# USB_SERIAL_QUAD.net
KiCad netlist of a schematic drawn in Altium Designer
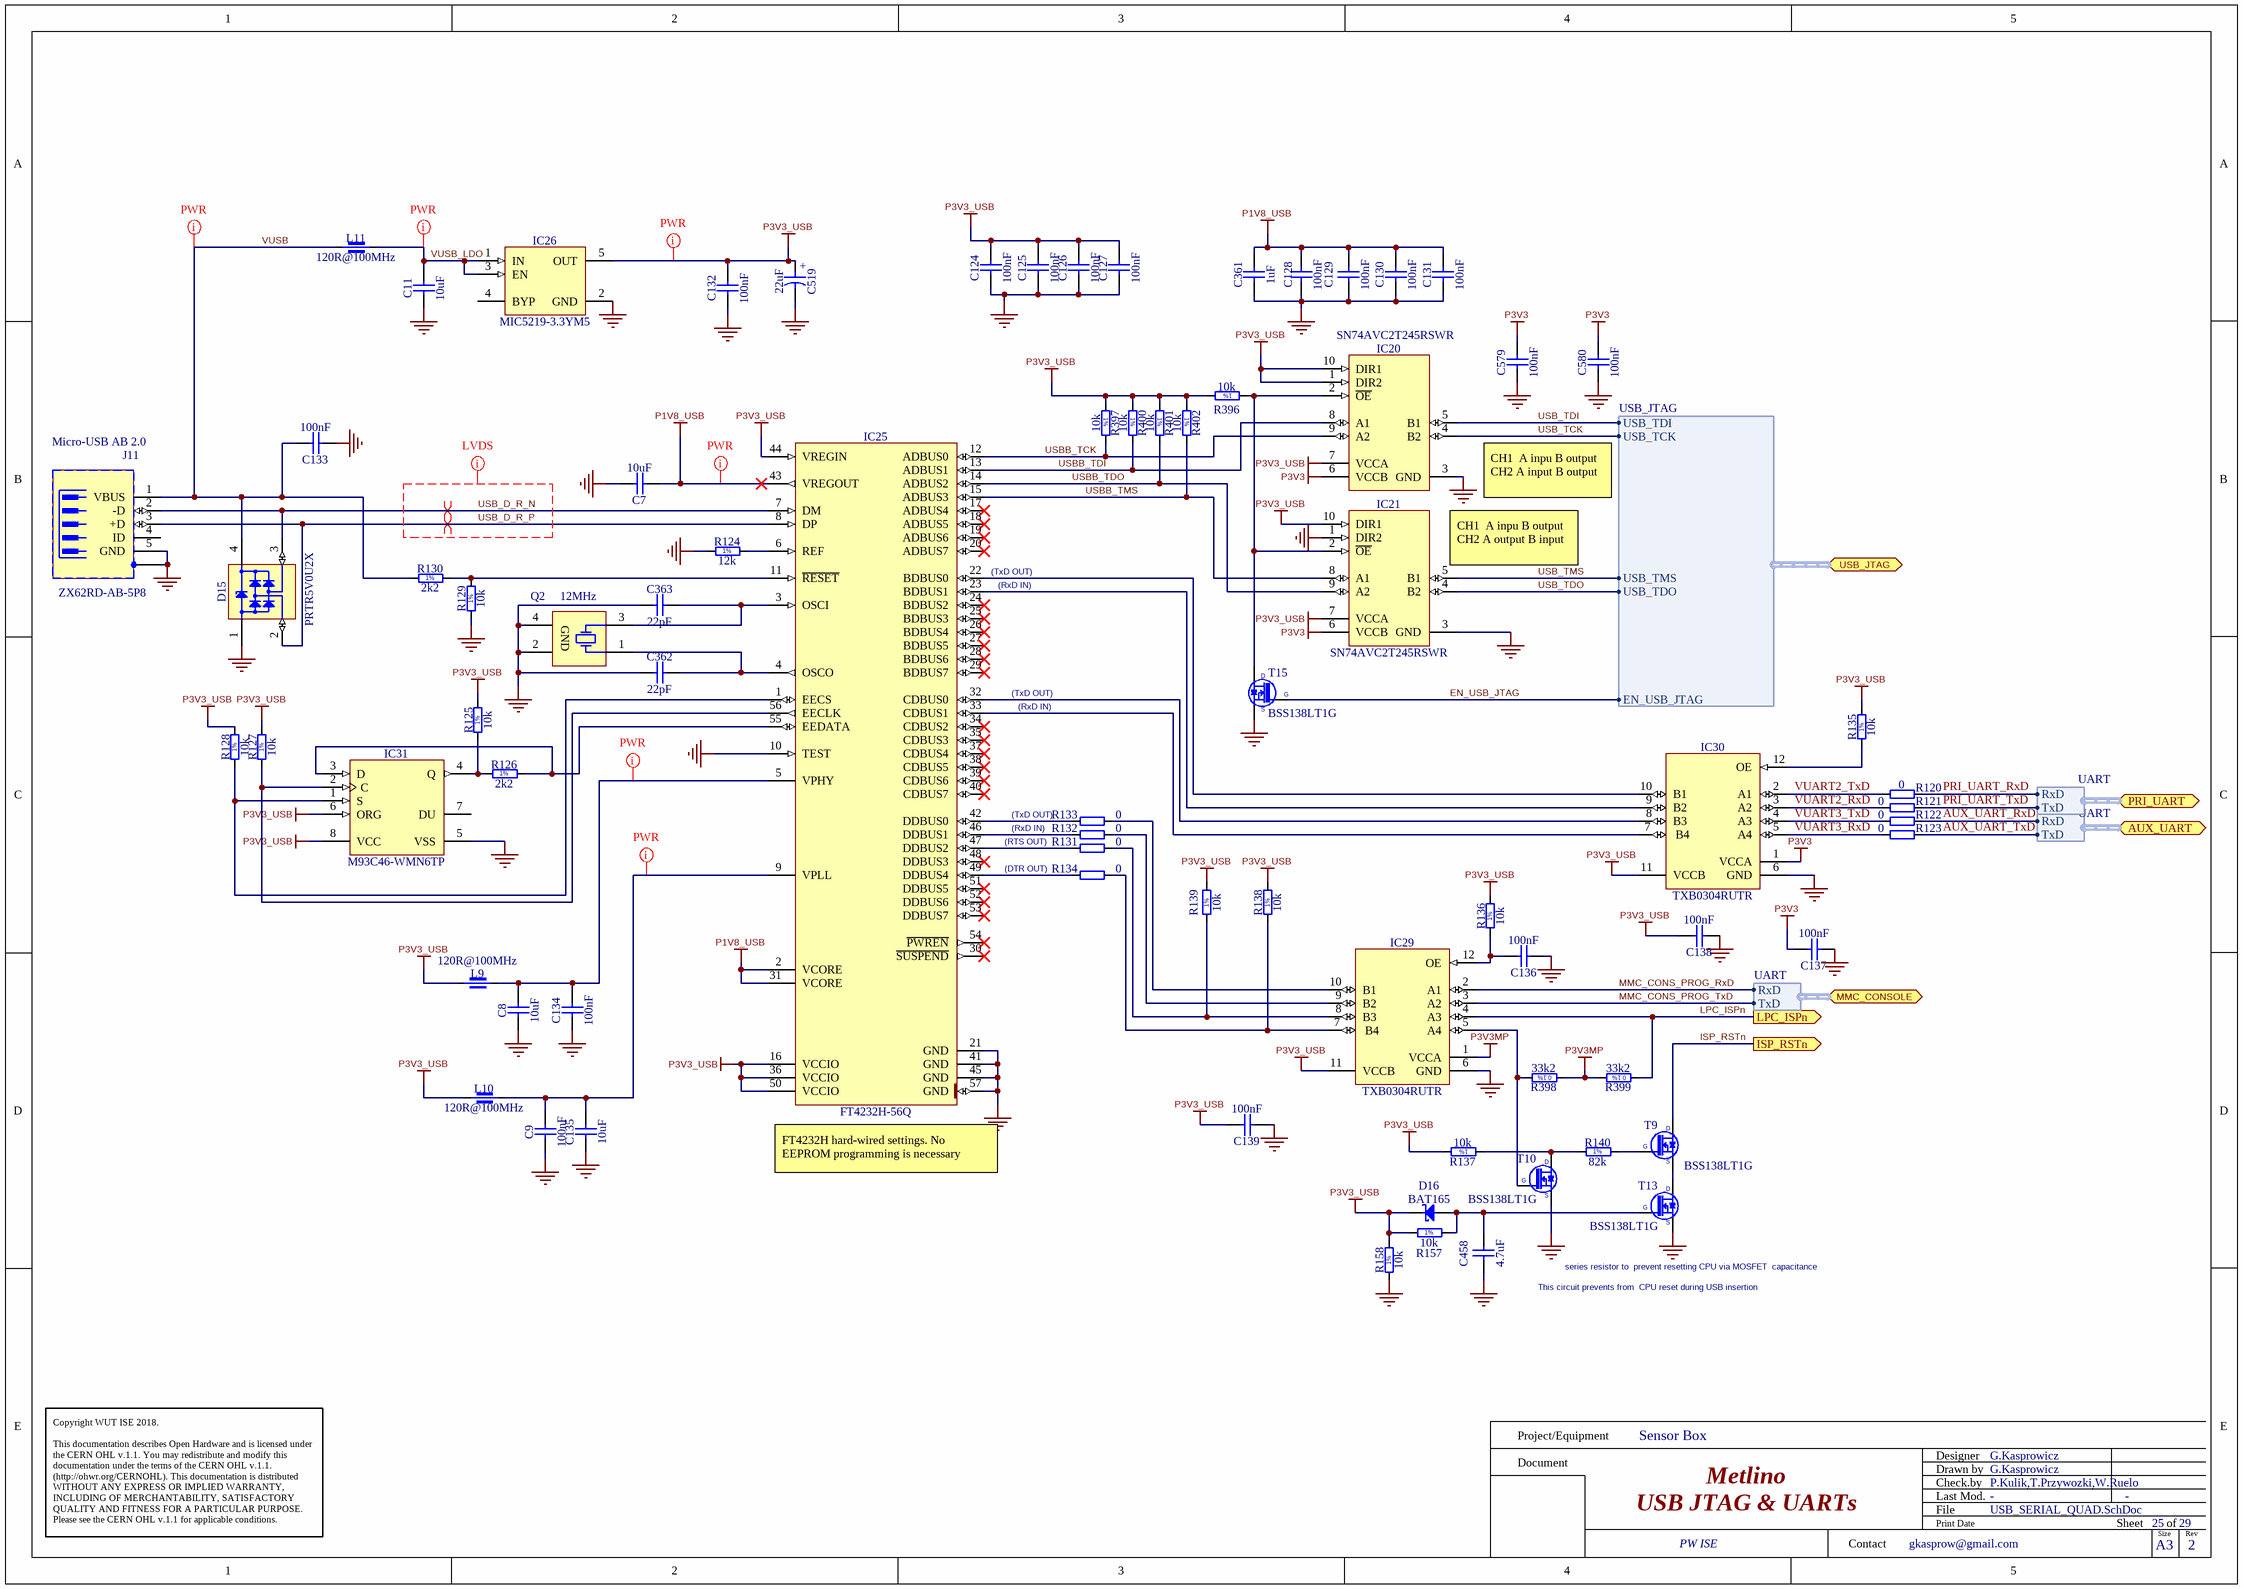
[diagram p0: USB_SERIAL_QUAD.SchDoc]

(export (version "E")
  (design (tool "Eeschema 10.0.6"))
  (components
    (comp (ref "C7")
      (value "10uF")
      (footprint "CAPC1608X87N")
      (description "Non-polarised capacitor")
      (fields
        (field (name "MANUFACTURER PART NUMBER") "CC0603_10uF_6.3V_20%_X5R")
        (field (name "MANUFACTURER") "GENERIC")
        (field (name "AUTHOR") "CERN DEM JLC")
      )
      (libsource (lib "Capacitors") (part "Capacitor - non polarized"))
    )
    (comp (ref "C8")
      (value "10uF")
      (footprint "CAPC1608X87N")
      (description "Non-polarised capacitor")
      (fields
        (field (name "MANUFACTURER PART NUMBER") "CC0603_10uF_6.3V_20%_X5R")
        (field (name "MANUFACTURER") "GENERIC")
        (field (name "AUTHOR") "CERN DEM JLC")
      )
      (libsource (lib "Capacitors") (part "Capacitor - non polarized"))
    )
    (comp (ref "C9")
      (value "100nF")
      (footprint "CAPC0603X33N")
      (description "Non-polarised capacitor")
      (fields
        (field (name "MANUFACTURER PART NUMBER") "CC0201_100NF_6.3V_10%_X5R")
        (field (name "MANUFACTURER") "GENERIC")
        (field (name "AUTHOR") "CERN DEM JLC")
      )
      (libsource (lib "Capacitors") (part "Capacitor - non polarized"))
    )
    (comp (ref "C11")
      (value "10uF")
      (footprint "CAPC1608X87N")
      (description "Non-polarised capacitor")
      (fields
        (field (name "MANUFACTURER PART NUMBER") "CC0603_10uF_6.3V_20%_X5R")
        (field (name "MANUFACTURER") "GENERIC")
        (field (name "AUTHOR") "CERN DEM JLC")
      )
      (libsource (lib "Capacitors") (part "Capacitor - non polarized"))
    )
    (comp (ref "C124")
      (value "100nF")
      (footprint "CAPC0603X33N")
      (description "Non-polarised capacitor")
      (fields
        (field (name "MANUFACTURER PART NUMBER") "CC0201_100NF_6.3V_10%_X5R")
        (field (name "MANUFACTURER") "GENERIC")
        (field (name "AUTHOR") "CERN DEM JLC")
      )
      (libsource (lib "Capacitors") (part "Capacitor - non polarized"))
    )
    (comp (ref "C125")
      (value "100nF")
      (footprint "CAPC0603X33N")
      (description "Non-polarised capacitor")
      (fields
        (field (name "MANUFACTURER PART NUMBER") "CC0201_100NF_6.3V_10%_X5R")
        (field (name "MANUFACTURER") "GENERIC")
        (field (name "AUTHOR") "CERN DEM JLC")
      )
      (libsource (lib "Capacitors") (part "Capacitor - non polarized"))
    )
    (comp (ref "C126")
      (value "100nF")
      (footprint "CAPC0603X33N")
      (description "Non-polarised capacitor")
      (fields
        (field (name "MANUFACTURER PART NUMBER") "CC0201_100NF_6.3V_10%_X5R")
        (field (name "MANUFACTURER") "GENERIC")
        (field (name "AUTHOR") "CERN DEM JLC")
      )
      (libsource (lib "Capacitors") (part "Capacitor - non polarized"))
    )
    (comp (ref "C127")
      (value "100nF")
      (footprint "CAPC0603X33N")
      (description "Non-polarised capacitor")
      (fields
        (field (name "MANUFACTURER PART NUMBER") "CC0201_100NF_6.3V_10%_X5R")
        (field (name "MANUFACTURER") "GENERIC")
        (field (name "AUTHOR") "CERN DEM JLC")
      )
      (libsource (lib "Capacitors") (part "Capacitor - non polarized"))
    )
    (comp (ref "C128")
      (value "100nF")
      (footprint "CAPC0603X33N")
      (description "Non-polarised capacitor")
      (fields
        (field (name "MANUFACTURER PART NUMBER") "CC0201_100NF_6.3V_10%_X5R")
        (field (name "MANUFACTURER") "GENERIC")
        (field (name "AUTHOR") "CERN DEM JLC")
      )
      (libsource (lib "Capacitors") (part "Capacitor - non polarized"))
    )
    (comp (ref "C129")
      (value "100nF")
      (footprint "CAPC0603X33N")
      (description "Non-polarised capacitor")
      (fields
        (field (name "MANUFACTURER PART NUMBER") "CC0201_100NF_6.3V_10%_X5R")
        (field (name "MANUFACTURER") "GENERIC")
        (field (name "AUTHOR") "CERN DEM JLC")
      )
      (libsource (lib "Capacitors") (part "Capacitor - non polarized"))
    )
    (comp (ref "C130")
      (value "100nF")
      (footprint "CAPC0603X33N")
      (description "Non-polarised capacitor")
      (fields
        (field (name "MANUFACTURER PART NUMBER") "CC0201_100NF_6.3V_10%_X5R")
        (field (name "MANUFACTURER") "GENERIC")
        (field (name "AUTHOR") "CERN DEM JLC")
      )
      (libsource (lib "Capacitors") (part "Capacitor - non polarized"))
    )
    (comp (ref "C131")
      (value "100nF")
      (footprint "CAPC0603X33N")
      (description "Non-polarised capacitor")
      (fields
        (field (name "MANUFACTURER PART NUMBER") "CC0201_100NF_6.3V_10%_X5R")
        (field (name "MANUFACTURER") "GENERIC")
        (field (name "AUTHOR") "CERN DEM JLC")
      )
      (libsource (lib "Capacitors") (part "Capacitor - non polarized"))
    )
    (comp (ref "C132")
      (value "100nF")
      (footprint "CAPC0603X33N")
      (description "Non-polarised capacitor")
      (fields
        (field (name "MANUFACTURER PART NUMBER") "CC0201_100NF_6.3V_10%_X5R")
        (field (name "MANUFACTURER") "GENERIC")
        (field (name "AUTHOR") "CERN DEM JLC")
      )
      (libsource (lib "Capacitors") (part "Capacitor - non polarized"))
    )
    (comp (ref "C133")
      (value "100nF")
      (footprint "CAPC0603X33N")
      (description "Non-polarised capacitor")
      (fields
        (field (name "MANUFACTURER PART NUMBER") "CC0201_100NF_6.3V_10%_X5R")
        (field (name "MANUFACTURER") "GENERIC")
        (field (name "AUTHOR") "CERN DEM JLC")
      )
      (libsource (lib "Capacitors") (part "Capacitor - non polarized"))
    )
    (comp (ref "C134")
      (value "100nF")
      (footprint "CAPC0603X33N")
      (description "Non-polarised capacitor")
      (fields
        (field (name "MANUFACTURER PART NUMBER") "CC0201_100NF_6.3V_10%_X5R")
        (field (name "MANUFACTURER") "GENERIC")
        (field (name "AUTHOR") "CERN DEM JLC")
      )
      (libsource (lib "Capacitors") (part "Capacitor - non polarized"))
    )
    (comp (ref "C135")
      (value "10uF")
      (footprint "CAPC1608X87N")
      (description "Non-polarised capacitor")
      (fields
        (field (name "MANUFACTURER PART NUMBER") "CC0603_10uF_6.3V_20%_X5R")
        (field (name "MANUFACTURER") "GENERIC")
        (field (name "AUTHOR") "CERN DEM JLC")
      )
      (libsource (lib "Capacitors") (part "Capacitor - non polarized"))
    )
    (comp (ref "C136")
      (value "100nF")
      (footprint "CAPC0603X33N")
      (description "Non-polarised capacitor")
      (fields
        (field (name "MANUFACTURER PART NUMBER") "CC0201_100NF_6.3V_10%_X5R")
        (field (name "MANUFACTURER") "GENERIC")
        (field (name "AUTHOR") "CERN DEM JLC")
      )
      (libsource (lib "Capacitors") (part "Capacitor - non polarized"))
    )
    (comp (ref "C137")
      (value "100nF")
      (footprint "CAPC0603X33N")
      (description "Non-polarised capacitor")
      (fields
        (field (name "MANUFACTURER PART NUMBER") "CC0201_100NF_6.3V_10%_X5R")
        (field (name "MANUFACTURER") "GENERIC")
        (field (name "AUTHOR") "CERN DEM JLC")
      )
      (libsource (lib "Capacitors") (part "Capacitor - non polarized"))
    )
    (comp (ref "C138")
      (value "100nF")
      (footprint "CAPC0603X33N")
      (description "Non-polarised capacitor")
      (fields
        (field (name "MANUFACTURER PART NUMBER") "CC0201_100NF_6.3V_10%_X5R")
        (field (name "MANUFACTURER") "GENERIC")
        (field (name "AUTHOR") "CERN DEM JLC")
      )
      (libsource (lib "Capacitors") (part "Capacitor - non polarized"))
    )
    (comp (ref "C139")
      (value "100nF")
      (footprint "CAPC0603X33N")
      (description "Non-polarised capacitor")
      (fields
        (field (name "MANUFACTURER PART NUMBER") "CC0201_100NF_6.3V_10%_X5R")
        (field (name "MANUFACTURER") "GENERIC")
        (field (name "AUTHOR") "CERN DEM JLC")
      )
      (libsource (lib "Capacitors") (part "Capacitor - non polarized"))
    )
    (comp (ref "C361")
      (value "1uF")
      (footprint "CAPC1005X55N")
      (description "Non-polarised capacitor")
      (fields
        (field (name "MANUFACTURER PART NUMBER") "CC0402_1UF_16V_10%_X5R")
        (field (name "MANUFACTURER") "GENERIC")
        (field (name "AUTHOR") "CERN DEM JLC")
      )
      (libsource (lib "Capacitors") (part "Capacitor - non polarized"))
    )
    (comp (ref "C362")
      (value "22pF")
      (footprint "CAPC1005X55N")
      (description "Non-polarised capacitor")
      (fields
        (field (name "MANUFACTURER PART NUMBER") "CC0402_22PF_50V_5%_C0G")
        (field (name "MANUFACTURER") "GENERIC")
        (field (name "AUTHOR") "CERN DEM JLC")
      )
      (libsource (lib "Capacitors") (part "Capacitor - non polarized"))
    )
    (comp (ref "C363")
      (value "22pF")
      (footprint "CAPC1005X55N")
      (description "Non-polarised capacitor")
      (fields
        (field (name "MANUFACTURER PART NUMBER") "CC0402_22PF_50V_5%_C0G")
        (field (name "MANUFACTURER") "GENERIC")
        (field (name "AUTHOR") "CERN DEM JLC")
      )
      (libsource (lib "Capacitors") (part "Capacitor - non polarized"))
    )
    (comp (ref "C458")
      (value "4.7uF")
      (footprint "CAPC1709X95N")
      (description "Non-polarised capacitor")
      (fields
        (field (name "MANUFACTURER PART NUMBER") "CC0603_4.7UF_16V_10%_X5R")
        (field (name "MANUFACTURER") "GENERIC")
        (field (name "AUTHOR") "CERN DEM JLC")
      )
      (libsource (lib "Capacitors") (part "Capacitor - non polarized"))
    )
    (comp (ref "C519")
      (value "22uF")
      (footprint "CAPMP3216X180N")
      (description "Polarised capacitor")
      (fields
        (field (name "MANUFACTURER PART NUMBER") "CTE3216-18_22UF_6.3V_10%_LESR0900")
        (field (name "MANUFACTURER") "GENERIC")
        (field (name "AUTHOR") "CERN DEM JLC")
      )
      (libsource (lib "Capacitors") (part "Capacitor - polarized"))
    )
    (comp (ref "C579")
      (value "100nF")
      (footprint "CAPC0603X33N")
      (description "Non-polarised capacitor")
      (fields
        (field (name "MANUFACTURER PART NUMBER") "CC0201_100NF_6.3V_10%_X5R")
        (field (name "MANUFACTURER") "GENERIC")
        (field (name "AUTHOR") "CERN DEM JLC")
      )
      (libsource (lib "Capacitors") (part "Capacitor - non polarized"))
    )
    (comp (ref "C580")
      (value "100nF")
      (footprint "CAPC0603X33N")
      (description "Non-polarised capacitor")
      (fields
        (field (name "MANUFACTURER PART NUMBER") "CC0201_100NF_6.3V_10%_X5R")
        (field (name "MANUFACTURER") "GENERIC")
        (field (name "AUTHOR") "CERN DEM JLC")
      )
      (libsource (lib "Capacitors") (part "Capacitor - non polarized"))
    )
    (comp (ref "D15")
      (value "PRTR5V0U2X")
      (footprint "SOT190P230X110-4N")
      (description "Ultra Low Capacitance Double Rail-to-Rail ESD Protection Diode")
      (fields
        (field (name "MANUFACTURER") "NXP SEMICONDUCTORS")
        (field (name "VOLTAGE") "5.5V")
        (field (name "AUTHOR") "CERN DEM JLC")
      )
      (libsource (lib "ICs And Semiconductors") (part "PRTR5V0U2X"))
    )
    (comp (ref "D16")
      (value "BAT165")
      (footprint "SOD2512X110N")
      (description "Schottky Diode")
      (fields
        (field (name "MANUFACTURER") "INFINEON")
        (field (name "VOLTAGE") "40V")
        (field (name "AUTHOR") "CERN DEM JLC")
      )
      (libsource (lib "ICs And Semiconductors") (part "Diode Schottky"))
    )
    (comp (ref "IC20")
      (value "SN74AVC2T245RSWR")
      (footprint "QFN40P140X180X55-10N")
      (description "Dual-Bit Dual-Supply Bus Transceiver With Configurable Voltage Translation and 3-State Outputs")
      (fields (field (name "MANUFACTURER") "TEXAS INSTRUMENTS") (field (name "AUTHOR") "CERN DEM JLC"))
      (libsource (lib "ICs And Semiconductors") (part "742T245"))
    )
    (comp (ref "IC21")
      (value "SN74AVC2T245RSWR")
      (footprint "QFN40P140X180X55-10N")
      (description "Dual-Bit Dual-Supply Bus Transceiver With Configurable Voltage Translation and 3-State Outputs")
      (fields (field (name "MANUFACTURER") "TEXAS INSTRUMENTS") (field (name "AUTHOR") "CERN DEM JLC"))
      (libsource (lib "ICs And Semiconductors") (part "742T245"))
    )
    (comp (ref "IC25")
      (value "FT4232H-56Q")
      (footprint "QFN50P800X800X100-57N-S620")
      (description "Quad High Speed USB to Multipurpose UART/MPSSE IC")
      (fields
        (field (name "MANUFACTURER") "FUTURE TECHNOLOGY DEVICES INTERNATIONAL (FTDI)")
        (field (name "AUTHOR") "CERN DEM JLC")
      )
      (libsource (lib "ICs And Semiconductors") (part "FT4232H-56Q"))
    )
    (comp (ref "IC26")
      (value "MIC5219-3.3YM5")
      (footprint "SOT95P280X145-5N")
      (description "500mA Peak Output LDO Regulator")
      (fields (field (name "MANUFACTURER") "MICROCHIP TECHNOLOGY") (field (name "AUTHOR") "CERN DEM WB"))
      (libsource (lib "ICs And Semiconductors") (part "MIC5219-X.XYM5"))
    )
    (comp (ref "IC29")
      (value "TXB0304RUTR")
      (footprint "TEXAS_RUT (R-PUQFN-N12)")
      (description "4-bit Bidirectional Auto-direction Sensing Translator with Fully Symmetric 0.9V to 3.6V Range")
      (fields (field (name "MANUFACTURER") "TEXAS INSTRUMENTS") (field (name "AUTHOR") "CERN DEM JLC"))
      (libsource (lib "ICs And Semiconductors") (part "TXB0304RUTR"))
    )
    (comp (ref "IC30")
      (value "TXB0304RUTR")
      (footprint "TEXAS_RUT (R-PUQFN-N12)")
      (description "4-bit Bidirectional Auto-direction Sensing Translator with Fully Symmetric 0.9V to 3.6V Range")
      (fields (field (name "MANUFACTURER") "TEXAS INSTRUMENTS") (field (name "AUTHOR") "CERN DEM JLC"))
      (libsource (lib "ICs And Semiconductors") (part "TXB0304RUTR"))
    )
    (comp (ref "IC31")
      (value "M93C46-WMN6TP")
      (footprint "SOIC127P600X175-8N")
      (description "2.5 to 5.5 V, 1Kb (128x8) Serial Microwire Bus EEPROM")
      (fields (field (name "MANUFACTURER") "ST MICROELECTRONICS") (field (name "AUTHOR") "CERN DEM JLC"))
      (libsource (lib "ICs And Semiconductors") (part "M93C46-WMN6TP"))
    )
    (comp (ref "J11")
      (value "Micro-USB AB 2.0")
      (footprint "HIROSE_ZX62RD-AB-5P8")
      (description "5 Pin + 1 Shield USB Receptacle")
      (fields
        (field (name "MANUFACTURER PART NUMBER") "ZX62RD-AB-5P8")
        (field (name "MANUFACTURER") "HIROSE (HRS)")
        (field (name "PART NUMBER") "HIROSE_ZX62RD-AB-5P8")
        (field (name "AUTHOR") "CERN DEM JLC")
      )
      (libsource (lib "Connectors") (part "Connector USB 5 Pin + 1Shield"))
    )
    (comp (ref "L9")
      (value "120R@100MHz")
      (footprint "INDC1608X65N")
      (fields
        (field (name "MANUFACTURER PART NUMBER") "BLM18SG121TN1D")
        (field (name "MANUFACTURER") "MURATA")
        (field (name "PART NUMBER") "IND0603_MURATA_BLM18SG121TN1D")
        (field (name "AUTHOR") "CERN DEM JLC")
      )
      (libsource (lib "Inductors & Transformers") (part "Ferrite Bead"))
    )
    (comp (ref "L10")
      (value "120R@100MHz")
      (footprint "INDC1608X65N")
      (fields
        (field (name "MANUFACTURER PART NUMBER") "BLM18SG121TN1D")
        (field (name "MANUFACTURER") "MURATA")
        (field (name "PART NUMBER") "IND0603_MURATA_BLM18SG121TN1D")
        (field (name "AUTHOR") "CERN DEM JLC")
      )
      (libsource (lib "Inductors & Transformers") (part "Ferrite Bead"))
    )
    (comp (ref "L11")
      (value "120R@100MHz")
      (footprint "INDC1608X65N")
      (fields
        (field (name "MANUFACTURER PART NUMBER") "BLM18SG121TN1D")
        (field (name "MANUFACTURER") "MURATA")
        (field (name "PART NUMBER") "IND0603_MURATA_BLM18SG121TN1D")
        (field (name "AUTHOR") "CERN DEM JLC")
      )
      (libsource (lib "Inductors & Transformers") (part "Ferrite Bead"))
    )
    (comp (ref "Q2")
      (value "12MHz")
      (footprint "XTAL_TXC_7M")
      (description "Crystal 4 pins 1=XTAL Control 2=GND3=XTAL 4=GND")
      (fields
        (field (name "MANUFACTURER PART NUMBER") "7M-12.000MAAJ-T")
        (field (name "MANUFACTURER") "TXC CORPORATION")
        (field (name "AUTHOR") "CERN DEM JLC")
      )
      (libsource (lib "ICs And Semiconductors") (part "Quartz Crystal 1X 2GND 3X 4GND"))
    )
    (comp (ref "R120")
      (value "0")
      (footprint "RESC1005X40N")
      (description "Resistor")
      (fields
        (field (name "MANUFACTURER PART NUMBER") "R0402_0R_JUMPER")
        (field (name "MANUFACTURER") "GENERIC")
        (field (name "AUTHOR") "CERN DEM JLC")
      )
      (libsource (lib "Resistors") (part "Resistor"))
    )
    (comp (ref "R121")
      (value "0")
      (footprint "RESC1005X40N")
      (description "Resistor")
      (fields
        (field (name "MANUFACTURER PART NUMBER") "R0402_0R_JUMPER")
        (field (name "MANUFACTURER") "GENERIC")
        (field (name "AUTHOR") "CERN DEM JLC")
      )
      (libsource (lib "Resistors") (part "Resistor"))
    )
    (comp (ref "R122")
      (value "0")
      (footprint "RESC1005X40N")
      (description "Resistor")
      (fields
        (field (name "MANUFACTURER PART NUMBER") "R0402_0R_JUMPER")
        (field (name "MANUFACTURER") "GENERIC")
        (field (name "AUTHOR") "CERN DEM JLC")
      )
      (libsource (lib "Resistors") (part "Resistor"))
    )
    (comp (ref "R123")
      (value "0")
      (footprint "RESC1005X40N")
      (description "Resistor")
      (fields
        (field (name "MANUFACTURER PART NUMBER") "R0402_0R_JUMPER")
        (field (name "MANUFACTURER") "GENERIC")
        (field (name "AUTHOR") "CERN DEM JLC")
      )
      (libsource (lib "Resistors") (part "Resistor"))
    )
    (comp (ref "R124")
      (value "12k")
      (footprint "RESC1005X40N")
      (description "Resistor - 1%")
      (fields
        (field (name "MANUFACTURER PART NUMBER") "R0402_12K_1%_0.0625W_100PPM")
        (field (name "MANUFACTURER") "GENERIC")
        (field (name "AUTHOR") "CERN DEM JLC")
      )
      (libsource (lib "Resistors") (part "Resistor - 1%"))
    )
    (comp (ref "R125")
      (value "10k")
      (footprint "RESC1005X40N")
      (description "Resistor - 1%")
      (fields
        (field (name "MANUFACTURER PART NUMBER") "R0402_10K_1%_0.0625W_100PPM")
        (field (name "MANUFACTURER") "GENERIC")
        (field (name "AUTHOR") "CERN DEM JLC")
      )
      (libsource (lib "Resistors") (part "Resistor - 1%"))
    )
    (comp (ref "R126")
      (value "2k2")
      (footprint "RESC1005X40N")
      (description "Resistor - 1%")
      (fields
        (field (name "MANUFACTURER PART NUMBER") "R0402_2K2_1%_0.0625W_100PPM")
        (field (name "MANUFACTURER") "GENERIC")
        (field (name "AUTHOR") "CERN DEM JLC")
      )
      (libsource (lib "Resistors") (part "Resistor - 1%"))
    )
    (comp (ref "R127")
      (value "10k")
      (footprint "RESC1005X40N")
      (description "Resistor - 1%")
      (fields
        (field (name "MANUFACTURER PART NUMBER") "R0402_10K_1%_0.0625W_100PPM")
        (field (name "MANUFACTURER") "GENERIC")
        (field (name "AUTHOR") "CERN DEM JLC")
      )
      (libsource (lib "Resistors") (part "Resistor - 1%"))
    )
    (comp (ref "R128")
      (value "10k")
      (footprint "RESC1005X40N")
      (description "Resistor - 1%")
      (fields
        (field (name "MANUFACTURER PART NUMBER") "R0402_10K_1%_0.0625W_100PPM")
        (field (name "MANUFACTURER") "GENERIC")
        (field (name "AUTHOR") "CERN DEM JLC")
      )
      (libsource (lib "Resistors") (part "Resistor - 1%"))
    )
    (comp (ref "R129")
      (value "10k")
      (footprint "RESC1005X40N")
      (description "Resistor - 1%")
      (fields
        (field (name "MANUFACTURER PART NUMBER") "R0402_10K_1%_0.0625W_100PPM")
        (field (name "MANUFACTURER") "GENERIC")
        (field (name "AUTHOR") "CERN DEM JLC")
      )
      (libsource (lib "Resistors") (part "Resistor - 1%"))
    )
    (comp (ref "R130")
      (value "2k2")
      (footprint "RESC1005X40N")
      (description "Resistor - 1%")
      (fields
        (field (name "MANUFACTURER PART NUMBER") "R0402_2K2_1%_0.0625W_100PPM")
        (field (name "MANUFACTURER") "GENERIC")
        (field (name "AUTHOR") "CERN DEM JLC")
      )
      (libsource (lib "Resistors") (part "Resistor - 1%"))
    )
    (comp (ref "R131")
      (value "0")
      (footprint "RESC1005X40N")
      (description "Resistor")
      (fields
        (field (name "MANUFACTURER PART NUMBER") "R0402_0R_JUMPER")
        (field (name "MANUFACTURER") "GENERIC")
        (field (name "AUTHOR") "CERN DEM JLC")
      )
      (libsource (lib "Resistors") (part "Resistor"))
    )
    (comp (ref "R132")
      (value "0")
      (footprint "RESC1005X40N")
      (description "Resistor")
      (fields
        (field (name "MANUFACTURER PART NUMBER") "R0402_0R_JUMPER")
        (field (name "MANUFACTURER") "GENERIC")
        (field (name "AUTHOR") "CERN DEM JLC")
      )
      (libsource (lib "Resistors") (part "Resistor"))
    )
    (comp (ref "R133")
      (value "0")
      (footprint "RESC1005X40N")
      (description "Resistor")
      (fields
        (field (name "MANUFACTURER PART NUMBER") "R0402_0R_JUMPER")
        (field (name "MANUFACTURER") "GENERIC")
        (field (name "AUTHOR") "CERN DEM JLC")
      )
      (libsource (lib "Resistors") (part "Resistor"))
    )
    (comp (ref "R134")
      (value "0")
      (footprint "RESC1005X40N")
      (description "Resistor")
      (fields
        (field (name "MANUFACTURER PART NUMBER") "R0402_0R_JUMPER")
        (field (name "MANUFACTURER") "GENERIC")
        (field (name "AUTHOR") "CERN DEM JLC")
      )
      (libsource (lib "Resistors") (part "Resistor"))
    )
    (comp (ref "R135")
      (value "10k")
      (footprint "RESC1005X40N")
      (description "Resistor - 1%")
      (fields
        (field (name "MANUFACTURER PART NUMBER") "R0402_10K_1%_0.0625W_100PPM")
        (field (name "MANUFACTURER") "GENERIC")
        (field (name "AUTHOR") "CERN DEM JLC")
      )
      (libsource (lib "Resistors") (part "Resistor - 1%"))
    )
    (comp (ref "R136")
      (value "10k")
      (footprint "RESC1005X40N")
      (description "Resistor - 1%")
      (fields
        (field (name "MANUFACTURER PART NUMBER") "R0402_10K_1%_0.0625W_100PPM")
        (field (name "MANUFACTURER") "GENERIC")
        (field (name "AUTHOR") "CERN DEM JLC")
      )
      (libsource (lib "Resistors") (part "Resistor - 1%"))
    )
    (comp (ref "R137")
      (value "10k")
      (footprint "RESC1005X40N")
      (description "Resistor - 1%")
      (fields
        (field (name "MANUFACTURER PART NUMBER") "R0402_10K_1%_0.0625W_100PPM")
        (field (name "MANUFACTURER") "GENERIC")
        (field (name "AUTHOR") "CERN DEM JLC")
      )
      (libsource (lib "Resistors") (part "Resistor - 1%"))
    )
    (comp (ref "R138")
      (value "10k")
      (footprint "RESC1005X40N")
      (description "Resistor - 1%")
      (fields
        (field (name "MANUFACTURER PART NUMBER") "R0402_10K_1%_0.0625W_100PPM")
        (field (name "MANUFACTURER") "GENERIC")
        (field (name "AUTHOR") "CERN DEM JLC")
      )
      (libsource (lib "Resistors") (part "Resistor - 1%"))
    )
    (comp (ref "R139")
      (value "10k")
      (footprint "RESC1005X40N")
      (description "Resistor - 1%")
      (fields
        (field (name "MANUFACTURER PART NUMBER") "R0402_10K_1%_0.0625W_100PPM")
        (field (name "MANUFACTURER") "GENERIC")
        (field (name "AUTHOR") "CERN DEM JLC")
      )
      (libsource (lib "Resistors") (part "Resistor - 1%"))
    )
    (comp (ref "R140")
      (value "82k")
      (footprint "RESC1005X40N")
      (description "Resistor - 1%")
      (fields
        (field (name "MANUFACTURER PART NUMBER") "R0402_82K_1%_0.0625W_100PPM")
        (field (name "MANUFACTURER") "GENERIC")
        (field (name "AUTHOR") "CERN DEM JLC")
      )
      (libsource (lib "Resistors") (part "Resistor - 1%"))
    )
    (comp (ref "R157")
      (value "10k")
      (footprint "RESC1005X40N")
      (description "Resistor - 1%")
      (fields
        (field (name "MANUFACTURER PART NUMBER") "R0402_10K_1%_0.0625W_100PPM")
        (field (name "MANUFACTURER") "GENERIC")
        (field (name "AUTHOR") "CERN DEM JLC")
      )
      (libsource (lib "Resistors") (part "Resistor - 1%"))
    )
    (comp (ref "R158")
      (value "10k")
      (footprint "RESC1005X40N")
      (description "Resistor - 1%")
      (fields
        (field (name "MANUFACTURER PART NUMBER") "R0402_10K_1%_0.0625W_100PPM")
        (field (name "MANUFACTURER") "GENERIC")
        (field (name "AUTHOR") "CERN DEM JLC")
      )
      (libsource (lib "Resistors") (part "Resistor - 1%"))
    )
    (comp (ref "R396")
      (value "10k")
      (footprint "RESC1005X40N")
      (description "Resistor - 1%")
      (fields
        (field (name "MANUFACTURER PART NUMBER") "R0402_10K_1%_0.0625W_100PPM")
        (field (name "MANUFACTURER") "GENERIC")
        (field (name "AUTHOR") "CERN DEM JLC")
      )
      (libsource (lib "Resistors") (part "Resistor - 1%"))
    )
    (comp (ref "R397")
      (value "10k")
      (footprint "RESC1005X40N")
      (description "Resistor - 1%")
      (fields
        (field (name "MANUFACTURER PART NUMBER") "R0402_10K_1%_0.0625W_100PPM")
        (field (name "MANUFACTURER") "GENERIC")
        (field (name "AUTHOR") "CERN DEM JLC")
      )
      (libsource (lib "Resistors") (part "Resistor - 1%"))
    )
    (comp (ref "R398")
      (value "33k2")
      (footprint "RESC1608X55N")
      (description "Resistor - 0.1%")
      (fields
        (field (name "MANUFACTURER PART NUMBER") "R0603_33K2_0.1%_0.063W_10PPM")
        (field (name "MANUFACTURER") "GENERIC")
        (field (name "AUTHOR") "CERN DEM JLC")
      )
      (libsource (lib "Resistors") (part "Resistor - 0.1%"))
    )
    (comp (ref "R399")
      (value "33k2")
      (footprint "RESC1608X55N")
      (description "Resistor - 0.1%")
      (fields
        (field (name "MANUFACTURER PART NUMBER") "R0603_33K2_0.1%_0.063W_10PPM")
        (field (name "MANUFACTURER") "GENERIC")
        (field (name "AUTHOR") "CERN DEM JLC")
      )
      (libsource (lib "Resistors") (part "Resistor - 0.1%"))
    )
    (comp (ref "R400")
      (value "10k")
      (footprint "RESC1005X40N")
      (description "Resistor - 1%")
      (fields
        (field (name "MANUFACTURER PART NUMBER") "R0402_10K_1%_0.0625W_100PPM")
        (field (name "MANUFACTURER") "GENERIC")
        (field (name "AUTHOR") "CERN DEM JLC")
      )
      (libsource (lib "Resistors") (part "Resistor - 1%"))
    )
    (comp (ref "R401")
      (value "10k")
      (footprint "RESC1005X40N")
      (description "Resistor - 1%")
      (fields
        (field (name "MANUFACTURER PART NUMBER") "R0402_10K_1%_0.0625W_100PPM")
        (field (name "MANUFACTURER") "GENERIC")
        (field (name "AUTHOR") "CERN DEM JLC")
      )
      (libsource (lib "Resistors") (part "Resistor - 1%"))
    )
    (comp (ref "R402")
      (value "10k")
      (footprint "RESC1005X40N")
      (description "Resistor - 1%")
      (fields
        (field (name "MANUFACTURER PART NUMBER") "R0402_10K_1%_0.0625W_100PPM")
        (field (name "MANUFACTURER") "GENERIC")
        (field (name "AUTHOR") "CERN DEM JLC")
      )
      (libsource (lib "Resistors") (part "Resistor - 1%"))
    )
    (comp (ref "T9")
      (value "BSS138LT1G")
      (footprint "SOT95P240X110-3N")
      (description "N-CHANNEL MOSFET WITH DIODE")
      (fields (field (name "MANUFACTURER") "ON SEMICONDUCTOR") (field (name "AUTHOR") "CERN DEM JLC"))
      (libsource (lib "ICs And Semiconductors") (part "N-MOSFET-D 1G 2S 3D"))
    )
    (comp (ref "T10")
      (value "BSS138LT1G")
      (footprint "SOT95P240X110-3N")
      (description "N-CHANNEL MOSFET WITH DIODE")
      (fields (field (name "MANUFACTURER") "ON SEMICONDUCTOR") (field (name "AUTHOR") "CERN DEM JLC"))
      (libsource (lib "ICs And Semiconductors") (part "N-MOSFET-D 1G 2S 3D"))
    )
    (comp (ref "T13")
      (value "BSS138LT1G")
      (footprint "SOT95P240X110-3N")
      (description "N-CHANNEL MOSFET WITH DIODE")
      (fields (field (name "MANUFACTURER") "ON SEMICONDUCTOR") (field (name "AUTHOR") "CERN DEM JLC"))
      (libsource (lib "ICs And Semiconductors") (part "N-MOSFET-D 1G 2S 3D"))
    )
    (comp (ref "T15")
      (value "BSS138LT1G")
      (footprint "SOT95P240X110-3N")
      (description "N-CHANNEL MOSFET WITH DIODE")
      (fields (field (name "MANUFACTURER") "ON SEMICONDUCTOR") (field (name "AUTHOR") "CERN DEM JLC"))
      (libsource (lib "") (part "N-MOSFET-D 1G 2S 3D_1"))
    )
  )
  (nets
    (net (code "4") (name "/AUX_UART_RxD") (class "Default")
      (node (ref "R122") (pin "1") (pinfunction "1_1") (pintype "passive"))
    )
    (net (code "5") (name "/AUX_UART_TxD") (class "Default")
      (node (ref "R123") (pin "1") (pinfunction "1_1") (pintype "passive"))
    )
    (net (code "6") (name "/EN_USB_JTAG") (class "Default")
      (node (ref "T15") (pin "1") (pinfunction "G_1") (pintype "passive"))
    )
    (net (code "7") (name "/ISP_RSTn") (class "Default")
      (node (ref "T9") (pin "3") (pinfunction "D_3") (pintype "passive"))
    )
    (net (code "8") (name "/LPC_ISPn") (class "Default")
      (node (ref "IC29") (pin "4") (pinfunction "A3_4") (pintype "bidirectional"))
      (node (ref "R399") (pin "1") (pinfunction "1_1") (pintype "passive"))
    )
    (net (code "9") (name "/MMC_CONS_PROG_RxD") (class "Default")
      (node (ref "IC29") (pin "2") (pinfunction "A1_2") (pintype "bidirectional"))
    )
    (net (code "10") (name "/MMC_CONS_PROG_TxD") (class "Default")
      (node (ref "IC29") (pin "3") (pinfunction "A2_3") (pintype "bidirectional"))
    )
    (net (code "11") (name "/PRI_UART_RxD") (class "Default")
      (node (ref "R120") (pin "1") (pinfunction "1_1") (pintype "passive"))
    )
    (net (code "12") (name "/PRI_UART_TxD") (class "Default")
      (node (ref "R121") (pin "1") (pinfunction "1_1") (pintype "passive"))
    )
    (net (code "14") (name "/USBB_TCK") (class "Default")
      (node (ref "IC20") (pin "9") (pinfunction "A2_9") (pintype "bidirectional"))
      (node (ref "IC25") (pin "12") (pinfunction "ADBUS0_12") (pintype "bidirectional"))
      (node (ref "R397") (pin "2") (pinfunction "2_2") (pintype "passive"))
    )
    (net (code "15") (name "/USBB_TDI") (class "Default")
      (node (ref "IC20") (pin "8") (pinfunction "A1_8") (pintype "bidirectional"))
      (node (ref "IC25") (pin "13") (pinfunction "ADBUS1_13") (pintype "bidirectional"))
      (node (ref "R400") (pin "2") (pinfunction "2_2") (pintype "passive"))
    )
    (net (code "16") (name "/USBB_TDO") (class "Default")
      (node (ref "IC21") (pin "9") (pinfunction "A2_9") (pintype "bidirectional"))
      (node (ref "IC25") (pin "14") (pinfunction "ADBUS2_14") (pintype "bidirectional"))
      (node (ref "R401") (pin "2") (pinfunction "2_2") (pintype "passive"))
    )
    (net (code "17") (name "/USBB_TMS") (class "Default")
      (node (ref "IC21") (pin "8") (pinfunction "A1_8") (pintype "bidirectional"))
      (node (ref "IC25") (pin "15") (pinfunction "ADBUS3_15") (pintype "bidirectional"))
      (node (ref "R402") (pin "2") (pinfunction "2_2") (pintype "passive"))
    )
    (net (code "18") (name "/USB_D_R_N") (class "Default")
      (node (ref "D15") (pin "3") (pinfunction "I/O2_3") (pintype "bidirectional"))
      (node (ref "IC25") (pin "7") (pinfunction "DM_7") (pintype "input"))
      (node (ref "J11") (pin "2") (pinfunction "-D_2") (pintype "bidirectional"))
    )
    (net (code "19") (name "/USB_D_R_P") (class "Default")
      (node (ref "D15") (pin "2") (pinfunction "I/O1_2") (pintype "bidirectional"))
      (node (ref "IC25") (pin "8") (pinfunction "DP_8") (pintype "input"))
      (node (ref "J11") (pin "3") (pinfunction "+D_3") (pintype "bidirectional"))
    )
    (net (code "20") (name "/USB_TCK") (class "Default")
      (node (ref "IC20") (pin "4") (pinfunction "B2_4") (pintype "bidirectional"))
    )
    (net (code "21") (name "/USB_TDI") (class "Default")
      (node (ref "IC20") (pin "5") (pinfunction "B1_5") (pintype "bidirectional"))
    )
    (net (code "22") (name "/USB_TDO") (class "Default")
      (node (ref "IC21") (pin "4") (pinfunction "B2_4") (pintype "bidirectional"))
    )
    (net (code "23") (name "/USB_TMS") (class "Default")
      (node (ref "IC21") (pin "5") (pinfunction "B1_5") (pintype "bidirectional"))
    )
    (net (code "24") (name "/VUART2_RxD") (class "Default")
      (node (ref "IC30") (pin "3") (pinfunction "A2_3") (pintype "bidirectional"))
      (node (ref "R121") (pin "2") (pinfunction "2_2") (pintype "passive"))
    )
    (net (code "25") (name "/VUART2_TxD") (class "Default")
      (node (ref "IC30") (pin "2") (pinfunction "A1_2") (pintype "bidirectional"))
      (node (ref "R120") (pin "2") (pinfunction "2_2") (pintype "passive"))
    )
    (net (code "26") (name "/VUART3_RxD") (class "Default")
      (node (ref "IC30") (pin "5") (pinfunction "A4_5") (pintype "bidirectional"))
      (node (ref "R123") (pin "2") (pinfunction "2_2") (pintype "passive"))
    )
    (net (code "27") (name "/VUART3_TxD") (class "Default")
      (node (ref "IC30") (pin "4") (pinfunction "A3_4") (pintype "bidirectional"))
      (node (ref "R122") (pin "2") (pinfunction "2_2") (pintype "passive"))
    )
    (net (code "28") (name "/VUSB") (class "Default")
      (node (ref "C133") (pin "2") (pinfunction "2_2") (pintype "passive"))
      (node (ref "D15") (pin "4") (pinfunction "VCC_4") (pintype "power_in"))
      (node (ref "J11") (pin "1") (pinfunction "VBUS_1") (pintype "power_in"))
      (node (ref "L11") (pin "1") (pinfunction "1_1") (pintype "passive"))
      (node (ref "R130") (pin "1") (pinfunction "1_1") (pintype "passive"))
    )
    (net (code "29") (name "/VUSB_LDO") (class "Default")
      (node (ref "C11") (pin "2") (pinfunction "2_2") (pintype "passive"))
      (node (ref "IC26") (pin "1") (pinfunction "IN_1") (pintype "input"))
      (node (ref "IC26") (pin "3") (pinfunction "EN_3") (pintype "input"))
      (node (ref "L11") (pin "2") (pinfunction "2_2") (pintype "passive"))
    )
    (net (code "32") (name "GND") (class "Default")
      (node (ref "C11") (pin "1") (pinfunction "1_1") (pintype "passive"))
      (node (ref "C124") (pin "1") (pinfunction "1_1") (pintype "passive"))
      (node (ref "C125") (pin "1") (pinfunction "1_1") (pintype "passive"))
      (node (ref "C126") (pin "1") (pinfunction "1_1") (pintype "passive"))
      (node (ref "C127") (pin "1") (pinfunction "1_1") (pintype "passive"))
      (node (ref "C128") (pin "1") (pinfunction "1_1") (pintype "passive"))
      (node (ref "C129") (pin "1") (pinfunction "1_1") (pintype "passive"))
      (node (ref "C130") (pin "1") (pinfunction "1_1") (pintype "passive"))
      (node (ref "C131") (pin "1") (pinfunction "1_1") (pintype "passive"))
      (node (ref "C132") (pin "1") (pinfunction "1_1") (pintype "passive"))
      (node (ref "C133") (pin "1") (pinfunction "1_1") (pintype "passive"))
      (node (ref "C134") (pin "1") (pinfunction "1_1") (pintype "passive"))
      (node (ref "C135") (pin "1") (pinfunction "1_1") (pintype "passive"))
      (node (ref "C136") (pin "1") (pinfunction "1_1") (pintype "passive"))
      (node (ref "C137") (pin "1") (pinfunction "1_1") (pintype "passive"))
      (node (ref "C138") (pin "1") (pinfunction "1_1") (pintype "passive"))
      (node (ref "C139") (pin "1") (pinfunction "1_1") (pintype "passive"))
      (node (ref "C361") (pin "2") (pinfunction "2_2") (pintype "passive"))
      (node (ref "C362") (pin "1") (pinfunction "1_1") (pintype "passive"))
      (node (ref "C363") (pin "1") (pinfunction "1_1") (pintype "passive"))
      (node (ref "C458") (pin "1") (pinfunction "1_1") (pintype "passive"))
      (node (ref "C519") (pin "2") (pinfunction "2_2") (pintype "passive"))
      (node (ref "C579") (pin "1") (pinfunction "1_1") (pintype "passive"))
      (node (ref "C580") (pin "1") (pinfunction "1_1") (pintype "passive"))
      (node (ref "C7") (pin "2") (pinfunction "2_2") (pintype "passive"))
      (node (ref "C8") (pin "1") (pinfunction "1_1") (pintype "passive"))
      (node (ref "C9") (pin "1") (pinfunction "1_1") (pintype "passive"))
      (node (ref "D15") (pin "1") (pinfunction "GND_1") (pintype "power_in"))
      (node (ref "IC20") (pin "3") (pinfunction "GND_3") (pintype "power_in"))
      (node (ref "IC21") (pin "1") (pinfunction "DIR2_1") (pintype "input"))
      (node (ref "IC21") (pin "3") (pinfunction "GND_3") (pintype "power_in"))
      (node (ref "IC25") (pin "10") (pinfunction "TEST_10") (pintype "input"))
      (node (ref "IC25") (pin "21") (pinfunction "GND_21") (pintype "power_in"))
      (node (ref "IC25") (pin "41") (pinfunction "GND_41") (pintype "power_in"))
      (node (ref "IC25") (pin "45") (pinfunction "GND_45") (pintype "power_in"))
      (node (ref "IC25") (pin "57") (pinfunction "GND_57") (pintype "bidirectional"))
      (node (ref "IC26") (pin "2") (pinfunction "GND_2") (pintype "power_in"))
      (node (ref "IC29") (pin "6") (pinfunction "GND_6") (pintype "power_in"))
      (node (ref "IC30") (pin "6") (pinfunction "GND_6") (pintype "power_in"))
      (node (ref "IC31") (pin "5") (pinfunction "VSS_5") (pintype "power_in"))
      (node (ref "J11") (pin "5") (pinfunction "GND_5") (pintype "power_in"))
      (node (ref "J11") (pin "6") (pinfunction "SH_6") (pintype "power_in"))
      (node (ref "Q2") (pin "2") (pinfunction "GND_2") (pintype "power_in"))
      (node (ref "Q2") (pin "4") (pinfunction "GND_4") (pintype "power_in"))
      (node (ref "R124") (pin "1") (pinfunction "1_1") (pintype "passive"))
      (node (ref "R129") (pin "1") (pinfunction "1_1") (pintype "passive"))
      (node (ref "R158") (pin "1") (pinfunction "1_1") (pintype "passive"))
      (node (ref "T10") (pin "2") (pinfunction "S_2") (pintype "passive"))
      (node (ref "T13") (pin "2") (pinfunction "S_2") (pintype "passive"))
      (node (ref "T15") (pin "2") (pinfunction "S_2") (pintype "passive"))
    )
    (net (code "33") (name "Net-(D16-A)") (class "Default")
      (node (ref "C458") (pin "2") (pinfunction "2_2") (pintype "passive"))
      (node (ref "D16") (pin "2") (pinfunction "A_2") (pintype "passive"))
      (node (ref "R157") (pin "2") (pinfunction "2_2") (pintype "passive"))
      (node (ref "T13") (pin "1") (pinfunction "G_1") (pintype "passive"))
    )
    (net (code "34") (name "Net-(IC20-~{OE})") (class "Default")
      (node (ref "IC20") (pin "2") (pinfunction "~{OE}_2") (pintype "input"))
      (node (ref "IC21") (pin "2") (pinfunction "~{OE}_2") (pintype "input"))
      (node (ref "R396") (pin "1") (pinfunction "1_1") (pintype "passive"))
      (node (ref "T15") (pin "3") (pinfunction "D_3") (pintype "passive"))
    )
    (net (code "35") (name "Net-(IC25-BDBUS0)") (class "Default")
      (node (ref "IC25") (pin "22") (pinfunction "BDBUS0_22") (pintype "bidirectional"))
      (node (ref "IC30") (pin "10") (pinfunction "B1_10") (pintype "bidirectional"))
    )
    (net (code "36") (name "Net-(IC25-BDBUS1)") (class "Default")
      (node (ref "IC25") (pin "23") (pinfunction "BDBUS1_23") (pintype "bidirectional"))
      (node (ref "IC30") (pin "9") (pinfunction "B2_9") (pintype "bidirectional"))
    )
    (net (code "37") (name "Net-(IC25-CDBUS0)") (class "Default")
      (node (ref "IC25") (pin "32") (pinfunction "CDBUS0_32") (pintype "bidirectional"))
      (node (ref "IC30") (pin "8") (pinfunction "B3_8") (pintype "bidirectional"))
    )
    (net (code "38") (name "Net-(IC25-CDBUS1)") (class "Default")
      (node (ref "IC25") (pin "33") (pinfunction "CDBUS1_33") (pintype "bidirectional"))
      (node (ref "IC30") (pin "7") (pinfunction "B4_7") (pintype "bidirectional"))
    )
    (net (code "39") (name "Net-(IC25-DDBUS0)") (class "Default")
      (node (ref "IC25") (pin "42") (pinfunction "DDBUS0_42") (pintype "bidirectional"))
      (node (ref "R133") (pin "1") (pinfunction "1_1") (pintype "passive"))
    )
    (net (code "40") (name "Net-(IC25-DDBUS1)") (class "Default")
      (node (ref "IC25") (pin "46") (pinfunction "DDBUS1_46") (pintype "bidirectional"))
      (node (ref "R132") (pin "1") (pinfunction "1_1") (pintype "passive"))
    )
    (net (code "41") (name "Net-(IC25-DDBUS2)") (class "Default")
      (node (ref "IC25") (pin "47") (pinfunction "DDBUS2_47") (pintype "bidirectional"))
      (node (ref "R131") (pin "1") (pinfunction "1_1") (pintype "passive"))
    )
    (net (code "42") (name "Net-(IC25-DDBUS4)") (class "Default")
      (node (ref "IC25") (pin "49") (pinfunction "DDBUS4_49") (pintype "bidirectional"))
      (node (ref "R134") (pin "1") (pinfunction "1_1") (pintype "passive"))
    )
    (net (code "43") (name "Net-(IC25-EECLK)") (class "Default")
      (node (ref "IC25") (pin "56") (pinfunction "EECLK_56") (pintype "output"))
      (node (ref "IC31") (pin "2") (pinfunction "C_2") (pintype "input"))
      (node (ref "R127") (pin "1") (pinfunction "1_1") (pintype "passive"))
    )
    (net (code "44") (name "Net-(IC25-EECS)") (class "Default")
      (node (ref "IC25") (pin "1") (pinfunction "EECS_1") (pintype "bidirectional"))
      (node (ref "IC31") (pin "1") (pinfunction "S_1") (pintype "input"))
      (node (ref "R128") (pin "1") (pinfunction "1_1") (pintype "passive"))
    )
    (net (code "45") (name "Net-(IC25-EEDATA)") (class "Default")
      (node (ref "IC25") (pin "55") (pinfunction "EEDATA_55") (pintype "bidirectional"))
      (node (ref "IC31") (pin "3") (pinfunction "D_3") (pintype "input"))
      (node (ref "R126") (pin "2") (pinfunction "2_2") (pintype "passive"))
    )
    (net (code "46") (name "Net-(IC25-OSCI)") (class "Default")
      (node (ref "C363") (pin "2") (pinfunction "2_2") (pintype "passive"))
      (node (ref "IC25") (pin "3") (pinfunction "OSCI_3") (pintype "input"))
      (node (ref "Q2") (pin "3") (pinfunction "X_3") (pintype "passive"))
    )
    (net (code "47") (name "Net-(IC25-OSCO)") (class "Default")
      (node (ref "C362") (pin "2") (pinfunction "2_2") (pintype "passive"))
      (node (ref "IC25") (pin "4") (pinfunction "OSCO_4") (pintype "output"))
      (node (ref "Q2") (pin "1") (pinfunction "X_1") (pintype "passive"))
    )
    (net (code "48") (name "Net-(IC25-REF)") (class "Default")
      (node (ref "IC25") (pin "6") (pinfunction "REF_6") (pintype "input"))
      (node (ref "R124") (pin "2") (pinfunction "2_2") (pintype "passive"))
    )
    (net (code "49") (name "Net-(IC25-VPHY)") (class "Default")
      (node (ref "C134") (pin "2") (pinfunction "2_2") (pintype "passive"))
      (node (ref "C8") (pin "2") (pinfunction "2_2") (pintype "passive"))
      (node (ref "IC25") (pin "5") (pinfunction "VPHY_5") (pintype "power_in"))
      (node (ref "L9") (pin "2") (pinfunction "2_2") (pintype "passive"))
    )
    (net (code "50") (name "Net-(IC25-VPLL)") (class "Default")
      (node (ref "C135") (pin "2") (pinfunction "2_2") (pintype "passive"))
      (node (ref "C9") (pin "2") (pinfunction "2_2") (pintype "passive"))
      (node (ref "IC25") (pin "9") (pinfunction "VPLL_9") (pintype "power_in"))
      (node (ref "L10") (pin "2") (pinfunction "2_2") (pintype "passive"))
    )
    (net (code "51") (name "Net-(IC25-~{RESET})") (class "Default")
      (node (ref "IC25") (pin "11") (pinfunction "~{RESET}_11") (pintype "input"))
      (node (ref "R129") (pin "2") (pinfunction "2_2") (pintype "passive"))
      (node (ref "R130") (pin "2") (pinfunction "2_2") (pintype "passive"))
    )
    (net (code "52") (name "Net-(IC29-A4)") (class "Default")
      (node (ref "IC29") (pin "5") (pinfunction "A4_5") (pintype "bidirectional"))
      (node (ref "R398") (pin "2") (pinfunction "2_2") (pintype "passive"))
      (node (ref "T10") (pin "1") (pinfunction "G_1") (pintype "passive"))
    )
    (net (code "53") (name "Net-(IC29-B1)") (class "Default")
      (node (ref "IC29") (pin "10") (pinfunction "B1_10") (pintype "bidirectional"))
      (node (ref "R133") (pin "2") (pinfunction "2_2") (pintype "passive"))
    )
    (net (code "54") (name "Net-(IC29-B2)") (class "Default")
      (node (ref "IC29") (pin "9") (pinfunction "B2_9") (pintype "bidirectional"))
      (node (ref "R132") (pin "2") (pinfunction "2_2") (pintype "passive"))
    )
    (net (code "55") (name "Net-(IC29-B3)") (class "Default")
      (node (ref "IC29") (pin "8") (pinfunction "B3_8") (pintype "bidirectional"))
      (node (ref "R131") (pin "2") (pinfunction "2_2") (pintype "passive"))
      (node (ref "R139") (pin "1") (pinfunction "1_1") (pintype "passive"))
    )
    (net (code "56") (name "Net-(IC29-B4)") (class "Default")
      (node (ref "IC29") (pin "7") (pinfunction "B4_7") (pintype "bidirectional"))
      (node (ref "R134") (pin "2") (pinfunction "2_2") (pintype "passive"))
      (node (ref "R138") (pin "1") (pinfunction "1_1") (pintype "passive"))
    )
    (net (code "57") (name "Net-(IC29-OE)") (class "Default")
      (node (ref "C136") (pin "2") (pinfunction "2_2") (pintype "passive"))
      (node (ref "IC29") (pin "12") (pinfunction "OE_12") (pintype "input"))
      (node (ref "R136") (pin "1") (pinfunction "1_1") (pintype "passive"))
    )
    (net (code "58") (name "Net-(IC30-OE)") (class "Default")
      (node (ref "IC30") (pin "12") (pinfunction "OE_12") (pintype "input"))
      (node (ref "R135") (pin "1") (pinfunction "1_1") (pintype "passive"))
    )
    (net (code "59") (name "Net-(IC31-Q)") (class "Default")
      (node (ref "IC31") (pin "4") (pinfunction "Q_4") (pintype "output"))
      (node (ref "R125") (pin "1") (pinfunction "1_1") (pintype "passive"))
      (node (ref "R126") (pin "1") (pinfunction "1_1") (pintype "passive"))
    )
    (net (code "60") (name "Net-(T9-G)") (class "Default")
      (node (ref "R140") (pin "2") (pinfunction "2_2") (pintype "passive"))
      (node (ref "T9") (pin "1") (pinfunction "G_1") (pintype "passive"))
    )
    (net (code "61") (name "Net-(T10-D)") (class "Default")
      (node (ref "R137") (pin "1") (pinfunction "1_1") (pintype "passive"))
      (node (ref "R140") (pin "1") (pinfunction "1_1") (pintype "passive"))
      (node (ref "T10") (pin "3") (pinfunction "D_3") (pintype "passive"))
    )
    (net (code "62") (name "Net-(T13-D)") (class "Default")
      (node (ref "T13") (pin "3") (pinfunction "D_3") (pintype "passive"))
      (node (ref "T9") (pin "2") (pinfunction "S_2") (pintype "passive"))
    )
    (net (code "63") (name "P1V8_USB") (class "Default")
      (node (ref "C128") (pin "2") (pinfunction "2_2") (pintype "passive"))
      (node (ref "C129") (pin "2") (pinfunction "2_2") (pintype "passive"))
      (node (ref "C130") (pin "2") (pinfunction "2_2") (pintype "passive"))
      (node (ref "C131") (pin "2") (pinfunction "2_2") (pintype "passive"))
      (node (ref "C361") (pin "1") (pinfunction "1_1") (pintype "passive"))
      (node (ref "C7") (pin "1") (pinfunction "1_1") (pintype "passive"))
      (node (ref "IC25") (pin "2") (pinfunction "VCORE_2") (pintype "power_in"))
      (node (ref "IC25") (pin "31") (pinfunction "VCORE_31") (pintype "power_in"))
      (node (ref "IC25") (pin "43") (pinfunction "VREGOUT_43") (pintype "output"))
    )
    (net (code "64") (name "P3V3") (class "Default")
      (node (ref "C137") (pin "2") (pinfunction "2_2") (pintype "passive"))
      (node (ref "C579") (pin "2") (pinfunction "2_2") (pintype "passive"))
      (node (ref "C580") (pin "2") (pinfunction "2_2") (pintype "passive"))
      (node (ref "IC20") (pin "6") (pinfunction "VCCB_6") (pintype "power_in"))
      (node (ref "IC21") (pin "6") (pinfunction "VCCB_6") (pintype "power_in"))
      (node (ref "IC30") (pin "1") (pinfunction "VCCA_1") (pintype "power_in"))
    )
    (net (code "65") (name "P3V3MP") (class "Default")
      (node (ref "IC29") (pin "1") (pinfunction "VCCA_1") (pintype "power_in"))
      (node (ref "R398") (pin "1") (pinfunction "1_1") (pintype "passive"))
      (node (ref "R399") (pin "2") (pinfunction "2_2") (pintype "passive"))
    )
    (net (code "66") (name "P3V3_USB") (class "Default")
      (node (ref "C124") (pin "2") (pinfunction "2_2") (pintype "passive"))
      (node (ref "C125") (pin "2") (pinfunction "2_2") (pintype "passive"))
      (node (ref "C126") (pin "2") (pinfunction "2_2") (pintype "passive"))
      (node (ref "C127") (pin "2") (pinfunction "2_2") (pintype "passive"))
      (node (ref "C132") (pin "2") (pinfunction "2_2") (pintype "passive"))
      (node (ref "C138") (pin "2") (pinfunction "2_2") (pintype "passive"))
      (node (ref "C139") (pin "2") (pinfunction "2_2") (pintype "passive"))
      (node (ref "C519") (pin "1") (pinfunction "1_1") (pintype "passive"))
      (node (ref "D16") (pin "1") (pinfunction "C_1") (pintype "passive"))
      (node (ref "IC20") (pin "1") (pinfunction "DIR2_1") (pintype "input"))
      (node (ref "IC20") (pin "10") (pinfunction "DIR1_10") (pintype "input"))
      (node (ref "IC20") (pin "7") (pinfunction "VCCA_7") (pintype "power_in"))
      (node (ref "IC21") (pin "10") (pinfunction "DIR1_10") (pintype "input"))
      (node (ref "IC21") (pin "7") (pinfunction "VCCA_7") (pintype "power_in"))
      (node (ref "IC25") (pin "16") (pinfunction "VCCIO_16") (pintype "power_in"))
      (node (ref "IC25") (pin "36") (pinfunction "VCCIO_36") (pintype "power_in"))
      (node (ref "IC25") (pin "44") (pinfunction "VREGIN_44") (pintype "input"))
      (node (ref "IC25") (pin "50") (pinfunction "VCCIO_50") (pintype "power_in"))
      (node (ref "IC26") (pin "5") (pinfunction "OUT_5") (pintype "power_in"))
      (node (ref "IC29") (pin "11") (pinfunction "VCCB_11") (pintype "power_in"))
      (node (ref "IC30") (pin "11") (pinfunction "VCCB_11") (pintype "power_in"))
      (node (ref "IC31") (pin "6") (pinfunction "ORG_6") (pintype "input"))
      (node (ref "IC31") (pin "8") (pinfunction "VCC_8") (pintype "power_in"))
      (node (ref "L10") (pin "1") (pinfunction "1_1") (pintype "passive"))
      (node (ref "L9") (pin "1") (pinfunction "1_1") (pintype "passive"))
      (node (ref "R125") (pin "2") (pinfunction "2_2") (pintype "passive"))
      (node (ref "R127") (pin "2") (pinfunction "2_2") (pintype "passive"))
      (node (ref "R128") (pin "2") (pinfunction "2_2") (pintype "passive"))
      (node (ref "R135") (pin "2") (pinfunction "2_2") (pintype "passive"))
      (node (ref "R136") (pin "2") (pinfunction "2_2") (pintype "passive"))
      (node (ref "R137") (pin "2") (pinfunction "2_2") (pintype "passive"))
      (node (ref "R138") (pin "2") (pinfunction "2_2") (pintype "passive"))
      (node (ref "R139") (pin "2") (pinfunction "2_2") (pintype "passive"))
      (node (ref "R157") (pin "1") (pinfunction "1_1") (pintype "passive"))
      (node (ref "R158") (pin "2") (pinfunction "2_2") (pintype "passive"))
      (node (ref "R396") (pin "2") (pinfunction "2_2") (pintype "passive"))
      (node (ref "R397") (pin "1") (pinfunction "1_1") (pintype "passive"))
      (node (ref "R400") (pin "1") (pinfunction "1_1") (pintype "passive"))
      (node (ref "R401") (pin "1") (pinfunction "1_1") (pintype "passive"))
      (node (ref "R402") (pin "1") (pinfunction "1_1") (pintype "passive"))
    )
    (net (code "67") (name "unconnected-(IC25-ADBUS4-Pad17)") (class "Default")
      (node (ref "IC25") (pin "17") (pinfunction "ADBUS4_17") (pintype "bidirectional+no_connect"))
    )
    (net (code "68") (name "unconnected-(IC25-ADBUS5-Pad18)") (class "Default")
      (node (ref "IC25") (pin "18") (pinfunction "ADBUS5_18") (pintype "bidirectional+no_connect"))
    )
    (net (code "69") (name "unconnected-(IC25-ADBUS6-Pad19)") (class "Default")
      (node (ref "IC25") (pin "19") (pinfunction "ADBUS6_19") (pintype "bidirectional+no_connect"))
    )
    (net (code "70") (name "unconnected-(IC25-ADBUS7-Pad20)") (class "Default")
      (node (ref "IC25") (pin "20") (pinfunction "ADBUS7_20") (pintype "bidirectional+no_connect"))
    )
    (net (code "71") (name "unconnected-(IC25-BDBUS2-Pad24)") (class "Default")
      (node (ref "IC25") (pin "24") (pinfunction "BDBUS2_24") (pintype "bidirectional+no_connect"))
    )
    (net (code "72") (name "unconnected-(IC25-BDBUS3-Pad25)") (class "Default")
      (node (ref "IC25") (pin "25") (pinfunction "BDBUS3_25") (pintype "bidirectional+no_connect"))
    )
    (net (code "73") (name "unconnected-(IC25-BDBUS4-Pad26)") (class "Default")
      (node (ref "IC25") (pin "26") (pinfunction "BDBUS4_26") (pintype "bidirectional+no_connect"))
    )
    (net (code "74") (name "unconnected-(IC25-BDBUS5-Pad27)") (class "Default")
      (node (ref "IC25") (pin "27") (pinfunction "BDBUS5_27") (pintype "bidirectional+no_connect"))
    )
    (net (code "75") (name "unconnected-(IC25-BDBUS6-Pad28)") (class "Default")
      (node (ref "IC25") (pin "28") (pinfunction "BDBUS6_28") (pintype "bidirectional+no_connect"))
    )
    (net (code "76") (name "unconnected-(IC25-BDBUS7-Pad29)") (class "Default")
      (node (ref "IC25") (pin "29") (pinfunction "BDBUS7_29") (pintype "bidirectional+no_connect"))
    )
    (net (code "77") (name "unconnected-(IC25-CDBUS2-Pad34)") (class "Default")
      (node (ref "IC25") (pin "34") (pinfunction "CDBUS2_34") (pintype "bidirectional+no_connect"))
    )
    (net (code "78") (name "unconnected-(IC25-CDBUS3-Pad35)") (class "Default")
      (node (ref "IC25") (pin "35") (pinfunction "CDBUS3_35") (pintype "bidirectional+no_connect"))
    )
    (net (code "79") (name "unconnected-(IC25-CDBUS4-Pad37)") (class "Default")
      (node (ref "IC25") (pin "37") (pinfunction "CDBUS4_37") (pintype "bidirectional+no_connect"))
    )
    (net (code "80") (name "unconnected-(IC25-CDBUS5-Pad38)") (class "Default")
      (node (ref "IC25") (pin "38") (pinfunction "CDBUS5_38") (pintype "bidirectional+no_connect"))
    )
    (net (code "81") (name "unconnected-(IC25-CDBUS6-Pad39)") (class "Default")
      (node (ref "IC25") (pin "39") (pinfunction "CDBUS6_39") (pintype "bidirectional+no_connect"))
    )
    (net (code "82") (name "unconnected-(IC25-CDBUS7-Pad40)") (class "Default")
      (node (ref "IC25") (pin "40") (pinfunction "CDBUS7_40") (pintype "bidirectional+no_connect"))
    )
    (net (code "83") (name "unconnected-(IC25-DDBUS3-Pad48)") (class "Default")
      (node (ref "IC25") (pin "48") (pinfunction "DDBUS3_48") (pintype "bidirectional+no_connect"))
    )
    (net (code "84") (name "unconnected-(IC25-DDBUS5-Pad51)") (class "Default")
      (node (ref "IC25") (pin "51") (pinfunction "DDBUS5_51") (pintype "bidirectional+no_connect"))
    )
    (net (code "85") (name "unconnected-(IC25-DDBUS6-Pad52)") (class "Default")
      (node (ref "IC25") (pin "52") (pinfunction "DDBUS6_52") (pintype "bidirectional+no_connect"))
    )
    (net (code "86") (name "unconnected-(IC25-DDBUS7-Pad53)") (class "Default")
      (node (ref "IC25") (pin "53") (pinfunction "DDBUS7_53") (pintype "bidirectional+no_connect"))
    )
    (net (code "87") (name "unconnected-(IC25-~{PWREN}-Pad54)") (class "Default")
      (node (ref "IC25") (pin "54") (pinfunction "~{PWREN}_54") (pintype "output+no_connect"))
    )
    (net (code "88") (name "unconnected-(IC25-~{SUSPEND}-Pad30)") (class "Default")
      (node (ref "IC25") (pin "30") (pinfunction "~{SUSPEND}_30") (pintype "output+no_connect"))
    )
    (net (code "89") (name "unconnected-(IC26-BYP-Pad4)") (class "Default")
      (node (ref "IC26") (pin "4") (pinfunction "BYP_4") (pintype "passive"))
    )
    (net (code "90") (name "unconnected-(IC31-DU-Pad7)") (class "Default")
      (node (ref "IC31") (pin "7") (pinfunction "DU_7") (pintype "passive"))
    )
    (net (code "91") (name "unconnected-(J11-ID-Pad4)") (class "Default")
      (node (ref "J11") (pin "4") (pinfunction "ID_4") (pintype "passive"))
    )
  )
)
